# vga.net
KiCad netlist of a schematic drawn in EAGLE
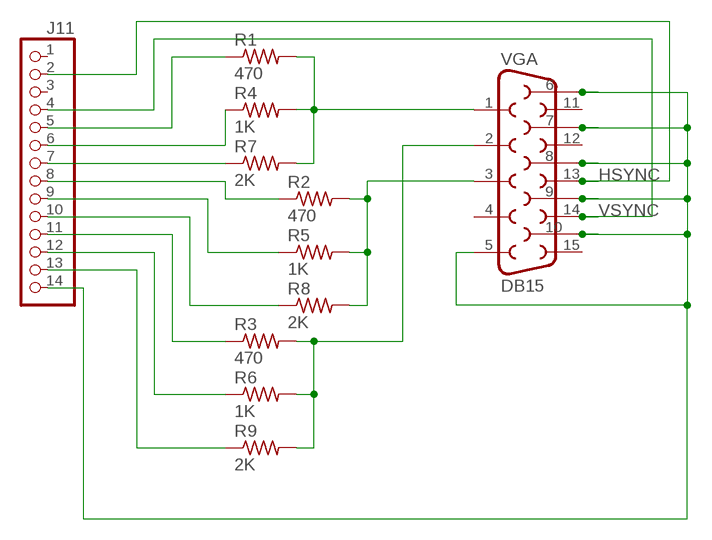
[diagram p0: schematic, sheet 1]

(export (version "E")
  (design (tool "Eeschema 10.0.6"))
  (components
    (comp (ref "J11")
      (value "PINHD-1X14")
      (footprint "eagle-import:1X14")
      (libsource (lib "eagle-import") (part "PINHD-1X14"))
    )
    (comp (ref "R1")
      (value "470")
      (footprint "eagle-import:R0805")
      (libsource (lib "eagle-import") (part "R-US_R0805"))
    )
    (comp (ref "R2")
      (value "470")
      (footprint "eagle-import:R0805")
      (libsource (lib "eagle-import") (part "R-US_R0805"))
    )
    (comp (ref "R3")
      (value "470")
      (footprint "eagle-import:R0805")
      (libsource (lib "eagle-import") (part "R-US_R0805"))
    )
    (comp (ref "R4")
      (value "1K")
      (footprint "eagle-import:R0805")
      (libsource (lib "eagle-import") (part "R-US_R0805"))
    )
    (comp (ref "R5")
      (value "1K")
      (footprint "eagle-import:R0805")
      (libsource (lib "eagle-import") (part "R-US_R0805"))
    )
    (comp (ref "R6")
      (value "1K")
      (footprint "eagle-import:R0805")
      (libsource (lib "eagle-import") (part "R-US_R0805"))
    )
    (comp (ref "R7")
      (value "2K")
      (footprint "eagle-import:R0805")
      (libsource (lib "eagle-import") (part "R-US_R0805"))
    )
    (comp (ref "R8")
      (value "2K")
      (footprint "eagle-import:R0805")
      (libsource (lib "eagle-import") (part "R-US_R0805"))
    )
    (comp (ref "R9")
      (value "2K")
      (footprint "eagle-import:R0805")
      (libsource (lib "eagle-import") (part "R-US_R0805"))
    )
    (comp (ref "VGA")
      (value "DB15")
      (footprint "eagle-import:DB15")
      (libsource (lib "eagle-import") (part "DB15"))
    )
  )
  (nets
    (net (code "1") (name "/HSYNC") (class "Default")
      (node (ref "J11") (pin "2") (pinfunction "2_2") (pintype "passive"))
      (node (ref "VGA") (pin "13") (pinfunction "13_13") (pintype "passive"))
    )
    (net (code "2") (name "/VSYNC") (class "Default")
      (node (ref "J11") (pin "4") (pinfunction "4_4") (pintype "passive"))
      (node (ref "VGA") (pin "14") (pinfunction "14_14") (pintype "passive"))
    )
    (net (code "3") (name "Net-(J11-Pad5)") (class "Default")
      (node (ref "J11") (pin "5") (pinfunction "5_5") (pintype "passive"))
      (node (ref "R1") (pin "1") (pinfunction "1_1") (pintype "passive"))
    )
    (net (code "4") (name "Net-(J11-Pad6)") (class "Default")
      (node (ref "J11") (pin "6") (pinfunction "6_6") (pintype "passive"))
      (node (ref "R4") (pin "1") (pinfunction "1_1") (pintype "passive"))
    )
    (net (code "5") (name "Net-(J11-Pad7)") (class "Default")
      (node (ref "J11") (pin "7") (pinfunction "7_7") (pintype "passive"))
      (node (ref "R7") (pin "1") (pinfunction "1_1") (pintype "passive"))
    )
    (net (code "6") (name "Net-(J11-Pad8)") (class "Default")
      (node (ref "J11") (pin "8") (pinfunction "8_8") (pintype "passive"))
      (node (ref "R2") (pin "1") (pinfunction "1_1") (pintype "passive"))
    )
    (net (code "7") (name "Net-(J11-Pad9)") (class "Default")
      (node (ref "J11") (pin "9") (pinfunction "9_9") (pintype "passive"))
      (node (ref "R5") (pin "1") (pinfunction "1_1") (pintype "passive"))
    )
    (net (code "8") (name "Net-(J11-Pad10)") (class "Default")
      (node (ref "J11") (pin "10") (pinfunction "10_10") (pintype "passive"))
      (node (ref "R8") (pin "1") (pinfunction "1_1") (pintype "passive"))
    )
    (net (code "9") (name "Net-(J11-Pad11)") (class "Default")
      (node (ref "J11") (pin "11") (pinfunction "11_11") (pintype "passive"))
      (node (ref "R3") (pin "1") (pinfunction "1_1") (pintype "passive"))
    )
    (net (code "10") (name "Net-(J11-Pad12)") (class "Default")
      (node (ref "J11") (pin "12") (pinfunction "12_12") (pintype "passive"))
      (node (ref "R6") (pin "1") (pinfunction "1_1") (pintype "passive"))
    )
    (net (code "11") (name "Net-(J11-Pad13)") (class "Default")
      (node (ref "J11") (pin "13") (pinfunction "13_13") (pintype "passive"))
      (node (ref "R9") (pin "1") (pinfunction "1_1") (pintype "passive"))
    )
    (net (code "12") (name "Net-(J11-Pad14)") (class "Default")
      (node (ref "J11") (pin "14") (pinfunction "14_14") (pintype "passive"))
      (node (ref "VGA") (pin "10") (pinfunction "10_10") (pintype "passive"))
      (node (ref "VGA") (pin "5") (pinfunction "5_5") (pintype "passive"))
      (node (ref "VGA") (pin "6") (pinfunction "6_6") (pintype "passive"))
      (node (ref "VGA") (pin "7") (pinfunction "7_7") (pintype "passive"))
      (node (ref "VGA") (pin "8") (pinfunction "8_8") (pintype "passive"))
      (node (ref "VGA") (pin "9") (pinfunction "9_9") (pintype "passive"))
    )
    (net (code "13") (name "Net-(R1-Pad2)") (class "Default")
      (node (ref "R1") (pin "2") (pinfunction "2_2") (pintype "passive"))
      (node (ref "R4") (pin "2") (pinfunction "2_2") (pintype "passive"))
      (node (ref "R7") (pin "2") (pinfunction "2_2") (pintype "passive"))
      (node (ref "VGA") (pin "1") (pinfunction "1_1") (pintype "passive"))
    )
    (net (code "14") (name "Net-(R2-Pad2)") (class "Default")
      (node (ref "R2") (pin "2") (pinfunction "2_2") (pintype "passive"))
      (node (ref "R5") (pin "2") (pinfunction "2_2") (pintype "passive"))
      (node (ref "R8") (pin "2") (pinfunction "2_2") (pintype "passive"))
      (node (ref "VGA") (pin "3") (pinfunction "3_3") (pintype "passive"))
    )
    (net (code "15") (name "Net-(R3-Pad2)") (class "Default")
      (node (ref "R3") (pin "2") (pinfunction "2_2") (pintype "passive"))
      (node (ref "R6") (pin "2") (pinfunction "2_2") (pintype "passive"))
      (node (ref "R9") (pin "2") (pinfunction "2_2") (pintype "passive"))
      (node (ref "VGA") (pin "2") (pinfunction "2_2") (pintype "passive"))
    )
    (net (code "16") (name "unconnected-(J11-Pad1)") (class "Default")
      (node (ref "J11") (pin "1") (pinfunction "1_1") (pintype "passive"))
    )
    (net (code "17") (name "unconnected-(J11-Pad3)") (class "Default")
      (node (ref "J11") (pin "3") (pinfunction "3_3") (pintype "passive"))
    )
    (net (code "18") (name "unconnected-(VGA-Pad4)") (class "Default")
      (node (ref "VGA") (pin "4") (pinfunction "4_4") (pintype "passive"))
    )
    (net (code "19") (name "unconnected-(VGA-Pad11)") (class "Default")
      (node (ref "VGA") (pin "11") (pinfunction "11_11") (pintype "passive"))
    )
    (net (code "20") (name "unconnected-(VGA-Pad12)") (class "Default")
      (node (ref "VGA") (pin "12") (pinfunction "12_12") (pintype "passive"))
    )
    (net (code "21") (name "unconnected-(VGA-Pad15)") (class "Default")
      (node (ref "VGA") (pin "15") (pinfunction "15_15") (pintype "passive"))
    )
  )
)
